# juliusledarray-v0_1.net
KiCad netlist of a schematic drawn in EAGLE
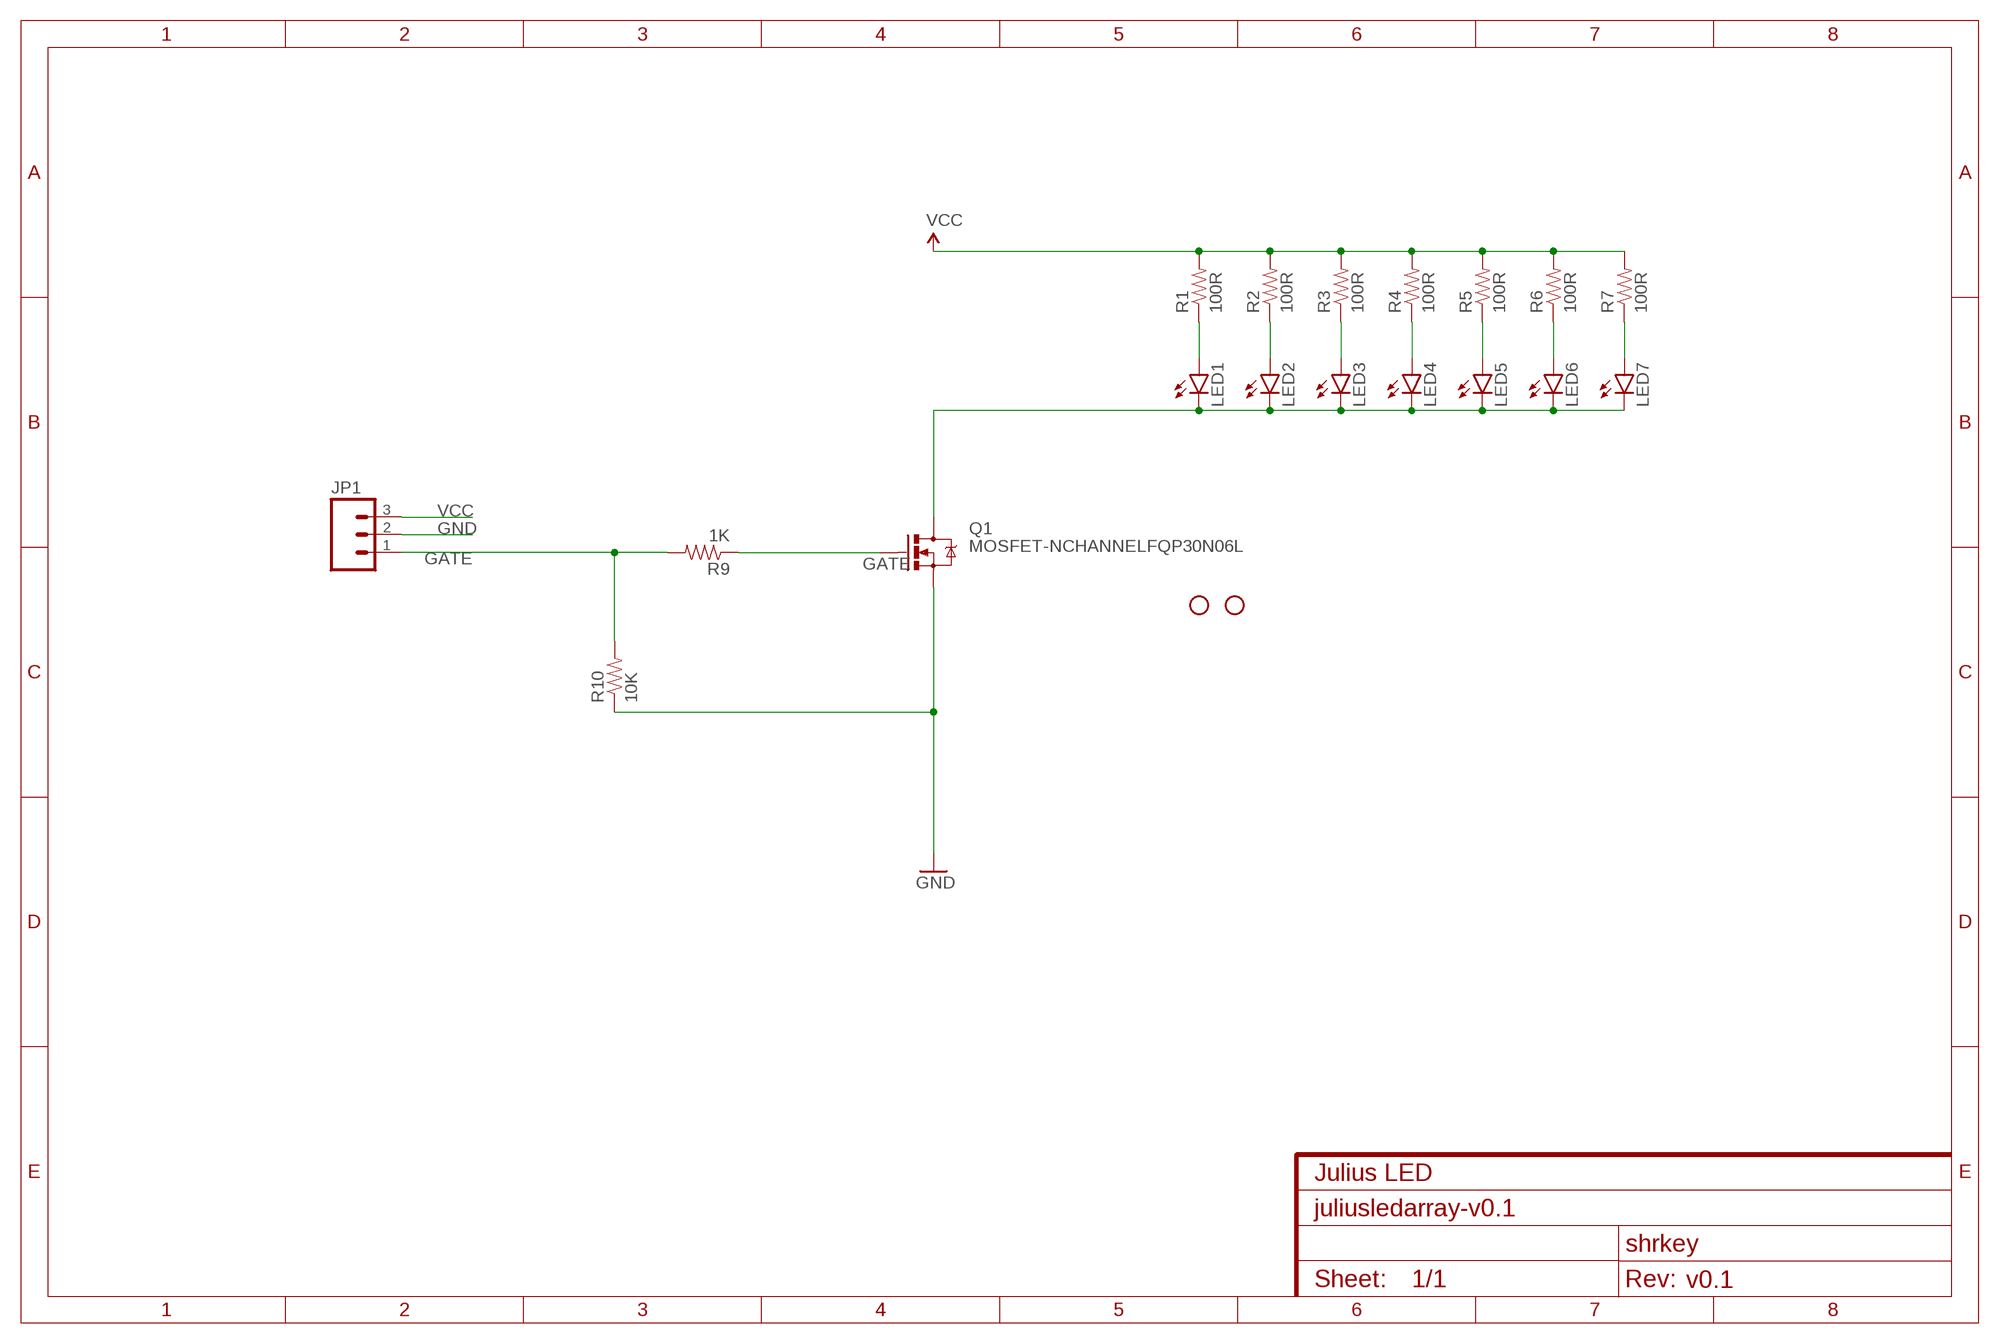
[diagram p0: schematic, sheet 1]

(export (version "E")
  (design (tool "Eeschema 10.0.6"))
  (components
    (comp (ref "JP1")
      (value "M03LOCK_LONGPADS")
      (footprint "eagle-import:1X03_LOCK_LONGPADS")
      (libsource (lib "eagle-import") (part "M03LOCK_LONGPADS"))
    )
    (comp (ref "LED1")
      (value "LED5MM")
      (footprint "eagle-import:LED5MM")
      (libsource (lib "eagle-import") (part "LED5MM"))
    )
    (comp (ref "LED2")
      (value "LED5MM")
      (footprint "eagle-import:LED5MM")
      (libsource (lib "eagle-import") (part "LED5MM"))
    )
    (comp (ref "LED3")
      (value "LED5MM")
      (footprint "eagle-import:LED5MM")
      (libsource (lib "eagle-import") (part "LED5MM"))
    )
    (comp (ref "LED4")
      (value "LED5MM")
      (footprint "eagle-import:LED5MM")
      (libsource (lib "eagle-import") (part "LED5MM"))
    )
    (comp (ref "LED5")
      (value "LED5MM")
      (footprint "eagle-import:LED5MM")
      (libsource (lib "eagle-import") (part "LED5MM"))
    )
    (comp (ref "LED6")
      (value "LED5MM")
      (footprint "eagle-import:LED5MM")
      (libsource (lib "eagle-import") (part "LED5MM"))
    )
    (comp (ref "LED7")
      (value "LED5MM")
      (footprint "eagle-import:LED5MM")
      (libsource (lib "eagle-import") (part "LED5MM"))
    )
    (comp (ref "Q1")
      (value "MOSFET-NCHANNELFQP30N06L")
      (footprint "eagle-import:TO220V")
      (libsource (lib "eagle-import") (part "MOSFET-NCHANNELFQP30N06L"))
    )
    (comp (ref "R1")
      (value "100R")
      (footprint "eagle-import:0805")
      (libsource (lib "eagle-import") (part "RESISTOR0805-RES"))
    )
    (comp (ref "R2")
      (value "100R")
      (footprint "eagle-import:0805")
      (libsource (lib "eagle-import") (part "RESISTOR0805-RES"))
    )
    (comp (ref "R3")
      (value "100R")
      (footprint "eagle-import:0805")
      (libsource (lib "eagle-import") (part "RESISTOR0805-RES"))
    )
    (comp (ref "R4")
      (value "100R")
      (footprint "eagle-import:0805")
      (libsource (lib "eagle-import") (part "RESISTOR0805-RES"))
    )
    (comp (ref "R5")
      (value "100R")
      (footprint "eagle-import:0805")
      (libsource (lib "eagle-import") (part "RESISTOR0805-RES"))
    )
    (comp (ref "R6")
      (value "100R")
      (footprint "eagle-import:0805")
      (libsource (lib "eagle-import") (part "RESISTOR0805-RES"))
    )
    (comp (ref "R7")
      (value "100R")
      (footprint "eagle-import:0805")
      (libsource (lib "eagle-import") (part "RESISTOR0805-RES"))
    )
    (comp (ref "R9")
      (value "1K")
      (footprint "eagle-import:0805")
      (libsource (lib "eagle-import") (part "RESISTOR0805-RES"))
    )
    (comp (ref "R10")
      (value "10K")
      (footprint "eagle-import:0805")
      (libsource (lib "eagle-import") (part "RESISTOR0805-RES"))
    )
    (comp (ref "STANDOFF1")
      (value "STAND-OFF")
      (footprint "eagle-import:STAND-OFF")
      (libsource (lib "eagle-import") (part "STAND-OFF"))
    )
    (comp (ref "STANDOFF2")
      (value "STAND-OFF")
      (footprint "eagle-import:STAND-OFF")
      (libsource (lib "eagle-import") (part "STAND-OFF"))
    )
  )
  (nets
    (net (code "1") (name "/GATE") (class "Default")
      (node (ref "JP1") (pin "1") (pinfunction "1_1") (pintype "passive"))
      (node (ref "R10") (pin "2") (pinfunction "2_2") (pintype "passive"))
      (node (ref "R9") (pin "2") (pinfunction "2_2") (pintype "passive"))
    )
    (net (code "2") (name "GND") (class "Default")
      (node (ref "JP1") (pin "2") (pinfunction "2_2") (pintype "passive"))
      (node (ref "Q1") (pin "3") (pinfunction "S_3") (pintype "passive"))
      (node (ref "R10") (pin "1") (pinfunction "1_1") (pintype "passive"))
    )
    (net (code "3") (name "Net-(LED1-C)") (class "Default")
      (node (ref "LED1") (pin "K") (pinfunction "C_K") (pintype "passive"))
      (node (ref "LED2") (pin "K") (pinfunction "C_K") (pintype "passive"))
      (node (ref "LED3") (pin "K") (pinfunction "C_K") (pintype "passive"))
      (node (ref "LED4") (pin "K") (pinfunction "C_K") (pintype "passive"))
      (node (ref "LED5") (pin "K") (pinfunction "C_K") (pintype "passive"))
      (node (ref "LED6") (pin "K") (pinfunction "C_K") (pintype "passive"))
      (node (ref "LED7") (pin "K") (pinfunction "C_K") (pintype "passive"))
      (node (ref "Q1") (pin "2") (pinfunction "D_2") (pintype "passive"))
    )
    (net (code "4") (name "Net-(LED1-PadA)") (class "Default")
      (node (ref "LED1") (pin "A") (pinfunction "A_A") (pintype "passive"))
      (node (ref "R1") (pin "1") (pinfunction "1_1") (pintype "passive"))
    )
    (net (code "5") (name "Net-(LED2-PadA)") (class "Default")
      (node (ref "LED2") (pin "A") (pinfunction "A_A") (pintype "passive"))
      (node (ref "R2") (pin "1") (pinfunction "1_1") (pintype "passive"))
    )
    (net (code "6") (name "Net-(LED3-PadA)") (class "Default")
      (node (ref "LED3") (pin "A") (pinfunction "A_A") (pintype "passive"))
      (node (ref "R3") (pin "1") (pinfunction "1_1") (pintype "passive"))
    )
    (net (code "7") (name "Net-(LED4-PadA)") (class "Default")
      (node (ref "LED4") (pin "A") (pinfunction "A_A") (pintype "passive"))
      (node (ref "R4") (pin "1") (pinfunction "1_1") (pintype "passive"))
    )
    (net (code "8") (name "Net-(LED5-PadA)") (class "Default")
      (node (ref "LED5") (pin "A") (pinfunction "A_A") (pintype "passive"))
      (node (ref "R5") (pin "1") (pinfunction "1_1") (pintype "passive"))
    )
    (net (code "9") (name "Net-(LED6-PadA)") (class "Default")
      (node (ref "LED6") (pin "A") (pinfunction "A_A") (pintype "passive"))
      (node (ref "R6") (pin "1") (pinfunction "1_1") (pintype "passive"))
    )
    (net (code "10") (name "Net-(LED7-PadA)") (class "Default")
      (node (ref "LED7") (pin "A") (pinfunction "A_A") (pintype "passive"))
      (node (ref "R7") (pin "1") (pinfunction "1_1") (pintype "passive"))
    )
    (net (code "11") (name "Net-(Q1-G)") (class "Default")
      (node (ref "Q1") (pin "1") (pinfunction "G_1") (pintype "passive"))
      (node (ref "R9") (pin "1") (pinfunction "1_1") (pintype "passive"))
    )
    (net (code "12") (name "VCC") (class "Default")
      (node (ref "JP1") (pin "3") (pinfunction "3_3") (pintype "passive"))
      (node (ref "R1") (pin "2") (pinfunction "2_2") (pintype "passive"))
      (node (ref "R2") (pin "2") (pinfunction "2_2") (pintype "passive"))
      (node (ref "R3") (pin "2") (pinfunction "2_2") (pintype "passive"))
      (node (ref "R4") (pin "2") (pinfunction "2_2") (pintype "passive"))
      (node (ref "R5") (pin "2") (pinfunction "2_2") (pintype "passive"))
      (node (ref "R6") (pin "2") (pinfunction "2_2") (pintype "passive"))
      (node (ref "R7") (pin "2") (pinfunction "2_2") (pintype "passive"))
    )
  )
)
